# InternetButtonBuzzer.net
KiCad netlist of a schematic drawn in EAGLE
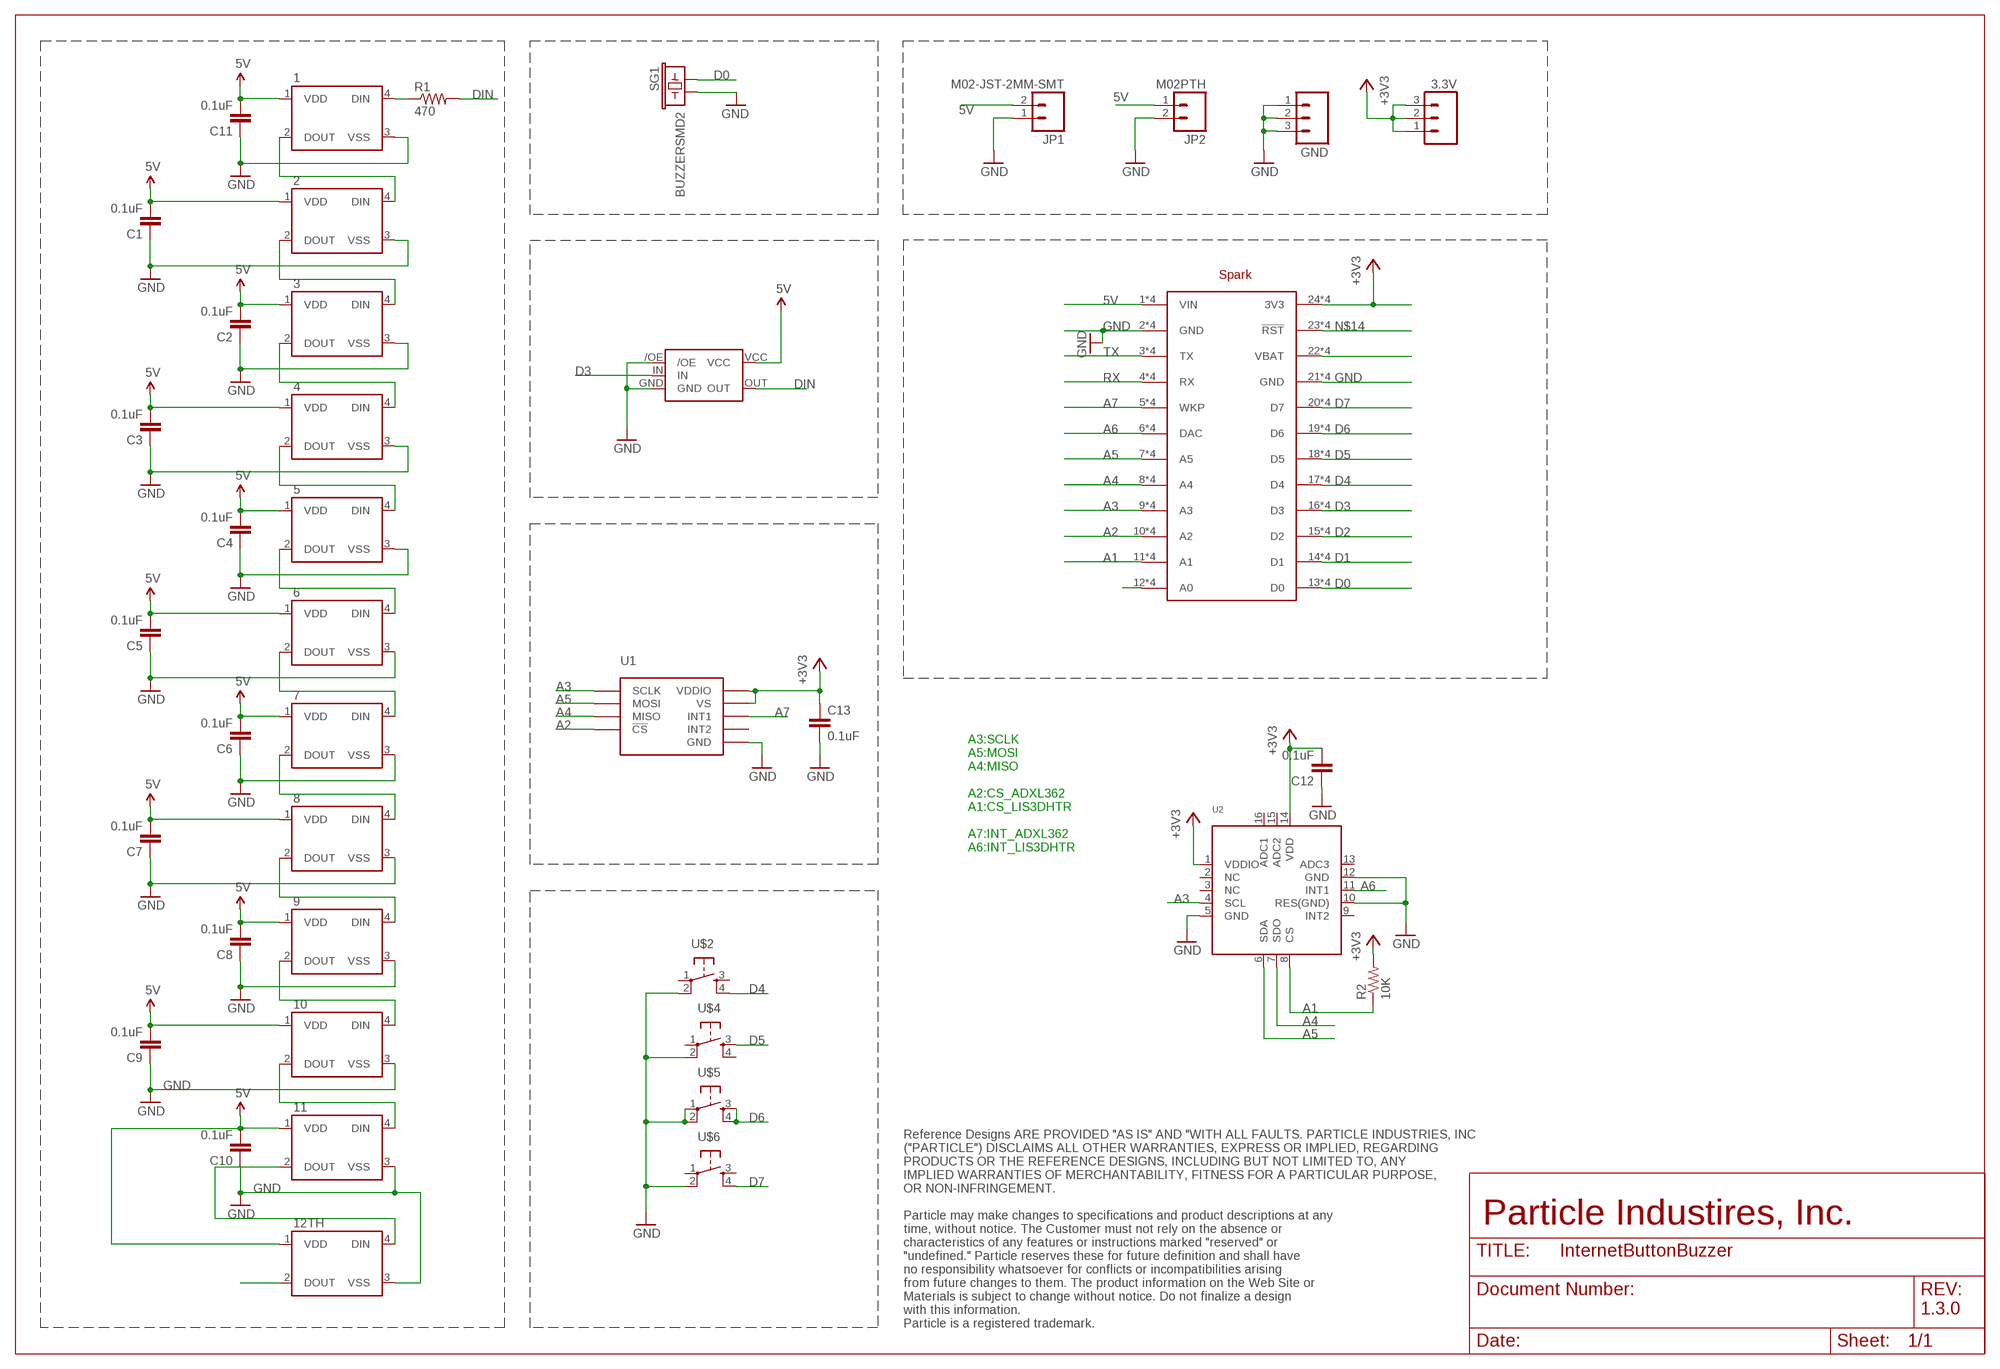
[diagram p0: schematic, sheet 1]

(export (version "E")
  (design (tool "Eeschema 10.0.6"))
  (components
    (comp (ref "1")
      (value "WS2812B")
      (footprint "eagle-import:WS2812B")
      (libsource (lib "eagle-import") (part "SparkFun-LED_WS2812B"))
    )
    (comp (ref "2")
      (value "WS2812B")
      (footprint "eagle-import:WS2812B")
      (libsource (lib "eagle-import") (part "SparkFun-LED_WS2812B"))
    )
    (comp (ref "3")
      (value "WS2812B")
      (footprint "eagle-import:WS2812B")
      (libsource (lib "eagle-import") (part "SparkFun-LED_WS2812B"))
    )
    (comp (ref "3.3V")
      (value "M03LOCK_NO_SILK")
      (footprint "eagle-import:1X03_LOCK_NO_SILK")
      (libsource (lib "eagle-import") (part "M03LOCK_NO_SILK"))
    )
    (comp (ref "4")
      (value "WS2812B")
      (footprint "eagle-import:WS2812B")
      (libsource (lib "eagle-import") (part "SparkFun-LED_WS2812B"))
    )
    (comp (ref "5")
      (value "WS2812B")
      (footprint "eagle-import:WS2812B")
      (libsource (lib "eagle-import") (part "SparkFun-LED_WS2812B"))
    )
    (comp (ref "6")
      (value "WS2812B")
      (footprint "eagle-import:WS2812B")
      (libsource (lib "eagle-import") (part "SparkFun-LED_WS2812B"))
    )
    (comp (ref "7")
      (value "WS2812B")
      (footprint "eagle-import:WS2812B")
      (libsource (lib "eagle-import") (part "SparkFun-LED_WS2812B"))
    )
    (comp (ref "8")
      (value "WS2812B")
      (footprint "eagle-import:WS2812B")
      (libsource (lib "eagle-import") (part "SparkFun-LED_WS2812B"))
    )
    (comp (ref "9")
      (value "WS2812B")
      (footprint "eagle-import:WS2812B")
      (libsource (lib "eagle-import") (part "SparkFun-LED_WS2812B"))
    )
    (comp (ref "10")
      (value "WS2812B")
      (footprint "eagle-import:WS2812B")
      (libsource (lib "eagle-import") (part "SparkFun-LED_WS2812B"))
    )
    (comp (ref "11")
      (value "WS2812B")
      (footprint "eagle-import:WS2812B")
      (libsource (lib "eagle-import") (part "SparkFun-LED_WS2812B"))
    )
    (comp (ref "12TH")
      (value "WS2812B")
      (footprint "eagle-import:NOCREAM_WS2812B")
      (libsource (lib "eagle-import") (part "WS2812B"))
    )
    (comp (ref "C1")
      (value "0.1uF")
      (footprint "eagle-import:0603-CAP")
      (libsource (lib "eagle-import") (part "15PF-50V-5%(0603)"))
    )
    (comp (ref "C2")
      (value "0.1uF")
      (footprint "eagle-import:0603-CAP")
      (libsource (lib "eagle-import") (part "15PF-50V-5%(0603)"))
    )
    (comp (ref "C3")
      (value "0.1uF")
      (footprint "eagle-import:0603-CAP")
      (libsource (lib "eagle-import") (part "15PF-50V-5%(0603)"))
    )
    (comp (ref "C4")
      (value "0.1uF")
      (footprint "eagle-import:0603-CAP")
      (libsource (lib "eagle-import") (part "15PF-50V-5%(0603)"))
    )
    (comp (ref "C5")
      (value "0.1uF")
      (footprint "eagle-import:0603-CAP")
      (libsource (lib "eagle-import") (part "15PF-50V-5%(0603)"))
    )
    (comp (ref "C6")
      (value "0.1uF")
      (footprint "eagle-import:0603-CAP")
      (libsource (lib "eagle-import") (part "15PF-50V-5%(0603)"))
    )
    (comp (ref "C7")
      (value "0.1uF")
      (footprint "eagle-import:0603-CAP")
      (libsource (lib "eagle-import") (part "15PF-50V-5%(0603)"))
    )
    (comp (ref "C8")
      (value "0.1uF")
      (footprint "eagle-import:0603-CAP")
      (libsource (lib "eagle-import") (part "15PF-50V-5%(0603)"))
    )
    (comp (ref "C9")
      (value "0.1uF")
      (footprint "eagle-import:0603-CAP")
      (libsource (lib "eagle-import") (part "15PF-50V-5%(0603)"))
    )
    (comp (ref "C10")
      (value "0.1uF")
      (footprint "eagle-import:0603-CAP")
      (libsource (lib "eagle-import") (part "15PF-50V-5%(0603)"))
    )
    (comp (ref "C11")
      (value "0.1uF")
      (footprint "eagle-import:0603-CAP")
      (libsource (lib "eagle-import") (part "15PF-50V-5%(0603)"))
    )
    (comp (ref "C12")
      (value "0.1uF")
      (footprint "eagle-import:0603-CAP")
      (libsource (lib "eagle-import") (part "CAP0603-CAP"))
    )
    (comp (ref "C13")
      (value "0.1uF")
      (footprint "eagle-import:0603-CAP")
      (libsource (lib "eagle-import") (part "CAP0603-CAP"))
    )
    (comp (ref "GND")
      (value "M03LOCK_NO_SILK")
      (footprint "eagle-import:1X03_LOCK_NO_SILK")
      (libsource (lib "eagle-import") (part "M03LOCK_NO_SILK"))
    )
    (comp (ref "JP1")
      (value "M02-JST-2MM-SMT")
      (footprint "eagle-import:JST-2-SMD")
      (libsource (lib "eagle-import") (part "M02-JST-2MM-SMT"))
    )
    (comp (ref "JP2")
      (value "M02PTH")
      (footprint "eagle-import:1X02")
      (libsource (lib "eagle-import") (part "M02PTH"))
    )
    (comp (ref "R1")
      (value "470")
      (footprint "eagle-import:0603-RES")
      (libsource (lib "eagle-import") (part "470OHM1/10W1%(0603)"))
    )
    (comp (ref "R2")
      (value "10K")
      (footprint "eagle-import:0603-RES")
      (libsource (lib "eagle-import") (part "470OHM1/10W1%(0603)"))
    )
    (comp (ref "SG1")
      (value "BUZZERSMD2")
      (footprint "eagle-import:BUZZER-CCV")
      (libsource (lib "eagle-import") (part "BUZZERSMD2"))
    )
    (comp (ref "U$2")
      (value "12MM_TACTILE_SWITCH")
      (footprint "eagle-import:12MM_TACTILE_SWITCH")
      (libsource (lib "eagle-import") (part "12MM_TACTILE_SWITCH"))
    )
    (comp (ref "U$3")
      (value "SPARK_LOGO_WITH_PLANE")
      (footprint "eagle-import:SPARK_LOGO_PLUS_PLANE")
      (libsource (lib "eagle-import") (part "SPARK_LOGO_WITH_PLANE"))
    )
    (comp (ref "U$4")
      (value "12MM_TACTILE_SWITCH")
      (footprint "eagle-import:12MM_TACTILE_SWITCH")
      (libsource (lib "eagle-import") (part "12MM_TACTILE_SWITCH"))
    )
    (comp (ref "U$5")
      (value "12MM_TACTILE_SWITCH")
      (footprint "eagle-import:12MM_TACTILE_SWITCH")
      (libsource (lib "eagle-import") (part "12MM_TACTILE_SWITCH"))
    )
    (comp (ref "U$6")
      (value "12MM_TACTILE_SWITCH")
      (footprint "eagle-import:12MM_TACTILE_SWITCH")
      (libsource (lib "eagle-import") (part "12MM_TACTILE_SWITCH"))
    )
    (comp (ref "U$7")
      (value "SPARK_COREDUAL_HEADER")
      (footprint "eagle-import:SPARK_CORE_DUAL_HEADER")
      (libsource (lib "eagle-import") (part "SPARK_COREDUAL_HEADER"))
    )
    (comp (ref "U$8")
      (value "NL17SZ125SOT553")
      (footprint "eagle-import:SOT-553")
      (libsource (lib "eagle-import") (part "NL17SZ125SOT553"))
    )
    (comp (ref "U1")
      (value "ADXL362ADXL362-1:1")
      (footprint "eagle-import:ADXL362-1_1")
      (libsource (lib "eagle-import") (part "ADXL362ADXL362-1{colon}1"))
    )
    (comp (ref "U2")
      (value "ACCEL_LIS3DHTR")
      (footprint "eagle-import:LGA16_3X3MM")
      (libsource (lib "eagle-import") (part "ACCEL_LIS3DHTR"))
    )
  )
  (nets
    (net (code "1") (name "+3V3") (class "Default")
      (node (ref "3.3V") (pin "1") (pinfunction "1_1") (pintype "passive"))
      (node (ref "3.3V") (pin "2") (pinfunction "2_2") (pintype "passive"))
      (node (ref "3.3V") (pin "3") (pinfunction "3_3") (pintype "passive"))
      (node (ref "C12") (pin "2") (pinfunction "2_2") (pintype "passive"))
      (node (ref "C13") (pin "1") (pinfunction "1_1") (pintype "passive"))
      (node (ref "R2") (pin "2") (pinfunction "2_2") (pintype "passive"))
      (node (ref "U$7") (pin "24") (pinfunction "3V3_24") (pintype "power_in"))
      (node (ref "U$7") (pin "24B") (pinfunction "3V3_24B") (pintype "power_in"))
      (node (ref "U$7") (pin "@24") (pinfunction "3V3_@24") (pintype "power_in"))
      (node (ref "U$7") (pin "@24B") (pinfunction "3V3_@24B") (pintype "power_in"))
      (node (ref "U1") (pin "P$1") (pinfunction "VDDIO_P$1") (pintype "bidirectional"))
      (node (ref "U1") (pin "P$14") (pinfunction "VS_P$14") (pintype "bidirectional"))
      (node (ref "U2") (pin "1") (pinfunction "VDDIO_1") (pintype "power_in"))
      (node (ref "U2") (pin "14") (pinfunction "VDD_14") (pintype "power_in"))
    )
    (net (code "2") (name "/A1") (class "Default")
      (node (ref "R2") (pin "1") (pinfunction "1_1") (pintype "passive"))
      (node (ref "U$7") (pin "11") (pinfunction "A1_11") (pintype "bidirectional"))
      (node (ref "U$7") (pin "11B") (pinfunction "A1_11B") (pintype "bidirectional"))
      (node (ref "U$7") (pin "@11") (pinfunction "A1_@11") (pintype "bidirectional"))
      (node (ref "U$7") (pin "@11B") (pinfunction "A1_@11B") (pintype "bidirectional"))
      (node (ref "U2") (pin "8") (pinfunction "CS_8") (pintype "input"))
    )
    (net (code "3") (name "/A2") (class "Default")
      (node (ref "U$7") (pin "10") (pinfunction "A2_10") (pintype "bidirectional"))
      (node (ref "U$7") (pin "10B") (pinfunction "A2_10B") (pintype "bidirectional"))
      (node (ref "U$7") (pin "@10") (pinfunction "A2_@10") (pintype "bidirectional"))
      (node (ref "U$7") (pin "@10B") (pinfunction "A2_@10B") (pintype "bidirectional"))
      (node (ref "U1") (pin "P$8") (pinfunction "~{CS}_P$8") (pintype "bidirectional"))
    )
    (net (code "4") (name "/A3") (class "Default")
      (node (ref "U$7") (pin "9") (pinfunction "A3_9") (pintype "bidirectional"))
      (node (ref "U$7") (pin "9B") (pinfunction "A3_9B") (pintype "bidirectional"))
      (node (ref "U$7") (pin "@9") (pinfunction "A3_@9") (pintype "bidirectional"))
      (node (ref "U$7") (pin "@9B") (pinfunction "A3_@9B") (pintype "bidirectional"))
      (node (ref "U1") (pin "P$4") (pinfunction "SCLK_P$4") (pintype "bidirectional"))
      (node (ref "U2") (pin "4") (pinfunction "SCL_4") (pintype "bidirectional"))
    )
    (net (code "5") (name "/A4") (class "Default")
      (node (ref "U$7") (pin "8") (pinfunction "A4_8") (pintype "bidirectional"))
      (node (ref "U$7") (pin "8B") (pinfunction "A4_8B") (pintype "bidirectional"))
      (node (ref "U$7") (pin "@8") (pinfunction "A4_@8") (pintype "bidirectional"))
      (node (ref "U$7") (pin "@8B") (pinfunction "A4_@8B") (pintype "bidirectional"))
      (node (ref "U1") (pin "P$7") (pinfunction "MISO_P$7") (pintype "bidirectional"))
      (node (ref "U2") (pin "7") (pinfunction "SDO_7") (pintype "bidirectional"))
    )
    (net (code "6") (name "/A5") (class "Default")
      (node (ref "U$7") (pin "7") (pinfunction "A5_7") (pintype "bidirectional"))
      (node (ref "U$7") (pin "7B") (pinfunction "A5_7B") (pintype "bidirectional"))
      (node (ref "U$7") (pin "@7") (pinfunction "A5_@7") (pintype "bidirectional"))
      (node (ref "U$7") (pin "@7B") (pinfunction "A5_@7B") (pintype "bidirectional"))
      (node (ref "U1") (pin "P$6") (pinfunction "MOSI_P$6") (pintype "bidirectional"))
      (node (ref "U2") (pin "6") (pinfunction "SDA_6") (pintype "bidirectional"))
    )
    (net (code "7") (name "/A6") (class "Default")
      (node (ref "U$7") (pin "6") (pinfunction "DAC_6") (pintype "bidirectional"))
      (node (ref "U$7") (pin "6B") (pinfunction "DAC_6B") (pintype "bidirectional"))
      (node (ref "U$7") (pin "@6") (pinfunction "DAC_@6") (pintype "bidirectional"))
      (node (ref "U$7") (pin "@6B") (pinfunction "DAC_@6B") (pintype "bidirectional"))
      (node (ref "U2") (pin "11") (pinfunction "INT1_11") (pintype "output"))
    )
    (net (code "8") (name "/A7") (class "Default")
      (node (ref "U$7") (pin "5") (pinfunction "WKP_5") (pintype "bidirectional"))
      (node (ref "U$7") (pin "5B") (pinfunction "WKP_5B") (pintype "bidirectional"))
      (node (ref "U$7") (pin "@5") (pinfunction "WKP_@5") (pintype "bidirectional"))
      (node (ref "U$7") (pin "@5B") (pinfunction "WKP_@5B") (pintype "bidirectional"))
      (node (ref "U1") (pin "P$11") (pinfunction "INT1_P$11") (pintype "bidirectional"))
    )
    (net (code "9") (name "/D0") (class "Default")
      (node (ref "SG1") (pin "+") (pinfunction "1_+") (pintype "passive"))
      (node (ref "U$7") (pin "13") (pinfunction "D0_13") (pintype "bidirectional"))
      (node (ref "U$7") (pin "13B") (pinfunction "D0_13B") (pintype "bidirectional"))
      (node (ref "U$7") (pin "@13") (pinfunction "D0_@13") (pintype "bidirectional"))
      (node (ref "U$7") (pin "@13B") (pinfunction "D0_@13B") (pintype "bidirectional"))
    )
    (net (code "10") (name "/D1") (class "Default")
      (node (ref "U$7") (pin "14") (pinfunction "D1_14") (pintype "bidirectional"))
      (node (ref "U$7") (pin "14B") (pinfunction "D1_14B") (pintype "bidirectional"))
      (node (ref "U$7") (pin "@14") (pinfunction "D1_@14") (pintype "bidirectional"))
      (node (ref "U$7") (pin "@14B") (pinfunction "D1_@14B") (pintype "bidirectional"))
    )
    (net (code "11") (name "/D2") (class "Default")
      (node (ref "U$7") (pin "15") (pinfunction "D2_15") (pintype "bidirectional"))
      (node (ref "U$7") (pin "15B") (pinfunction "D2_15B") (pintype "bidirectional"))
      (node (ref "U$7") (pin "@15") (pinfunction "D2_@15") (pintype "bidirectional"))
      (node (ref "U$7") (pin "@15B") (pinfunction "D2_@15B") (pintype "bidirectional"))
    )
    (net (code "12") (name "/D3") (class "Default")
      (node (ref "U$7") (pin "16") (pinfunction "D3_16") (pintype "bidirectional"))
      (node (ref "U$7") (pin "16B") (pinfunction "D3_16B") (pintype "bidirectional"))
      (node (ref "U$7") (pin "@16") (pinfunction "D3_@16") (pintype "bidirectional"))
      (node (ref "U$7") (pin "@16B") (pinfunction "D3_@16B") (pintype "bidirectional"))
      (node (ref "U$8") (pin "IN") (pinfunction "IN_IN") (pintype "bidirectional"))
    )
    (net (code "13") (name "/D4") (class "Default")
      (node (ref "U$2") (pin "4") (pinfunction "4_4") (pintype "passive"))
      (node (ref "U$7") (pin "17") (pinfunction "D4_17") (pintype "bidirectional"))
      (node (ref "U$7") (pin "17B") (pinfunction "D4_17B") (pintype "bidirectional"))
      (node (ref "U$7") (pin "@17") (pinfunction "D4_@17") (pintype "bidirectional"))
      (node (ref "U$7") (pin "@17B") (pinfunction "D4_@17B") (pintype "bidirectional"))
    )
    (net (code "14") (name "/D5") (class "Default")
      (node (ref "U$4") (pin "3") (pinfunction "3_3") (pintype "passive"))
      (node (ref "U$7") (pin "18") (pinfunction "D5_18") (pintype "bidirectional"))
      (node (ref "U$7") (pin "18B") (pinfunction "D5_18B") (pintype "bidirectional"))
      (node (ref "U$7") (pin "@18") (pinfunction "D5_@18") (pintype "bidirectional"))
      (node (ref "U$7") (pin "@18B") (pinfunction "D5_@18B") (pintype "bidirectional"))
    )
    (net (code "15") (name "/D6") (class "Default")
      (node (ref "U$5") (pin "3") (pinfunction "3_3") (pintype "passive"))
      (node (ref "U$5") (pin "4") (pinfunction "4_4") (pintype "passive"))
      (node (ref "U$7") (pin "19") (pinfunction "D6_19") (pintype "bidirectional"))
      (node (ref "U$7") (pin "19B") (pinfunction "D6_19B") (pintype "bidirectional"))
      (node (ref "U$7") (pin "@19") (pinfunction "D6_@19") (pintype "bidirectional"))
      (node (ref "U$7") (pin "@19B") (pinfunction "D6_@19B") (pintype "bidirectional"))
    )
    (net (code "16") (name "/D7") (class "Default")
      (node (ref "U$6") (pin "4") (pinfunction "4_4") (pintype "passive"))
      (node (ref "U$7") (pin "20") (pinfunction "D7_20") (pintype "bidirectional"))
      (node (ref "U$7") (pin "20B") (pinfunction "D7_20B") (pintype "bidirectional"))
      (node (ref "U$7") (pin "@20") (pinfunction "D7_@20") (pintype "bidirectional"))
      (node (ref "U$7") (pin "@20B") (pinfunction "D7_@20B") (pintype "bidirectional"))
    )
    (net (code "17") (name "/DIN") (class "Default")
      (node (ref "R1") (pin "2") (pinfunction "2_2") (pintype "passive"))
      (node (ref "U$8") (pin "OUT") (pinfunction "OUT_OUT") (pintype "bidirectional"))
    )
    (net (code "18") (name "/N$14") (class "Default")
      (node (ref "U$7") (pin "23") (pinfunction "~{RST}_23") (pintype "bidirectional"))
      (node (ref "U$7") (pin "23B") (pinfunction "~{RST}_23B") (pintype "bidirectional"))
      (node (ref "U$7") (pin "@23") (pinfunction "~{RST}_@23") (pintype "bidirectional"))
      (node (ref "U$7") (pin "@23B") (pinfunction "~{RST}_@23B") (pintype "bidirectional"))
    )
    (net (code "19") (name "/RX") (class "Default")
      (node (ref "U$7") (pin "4") (pinfunction "RX_4") (pintype "bidirectional"))
      (node (ref "U$7") (pin "4B") (pinfunction "RX_4B") (pintype "bidirectional"))
      (node (ref "U$7") (pin "@4") (pinfunction "RX_@4") (pintype "bidirectional"))
      (node (ref "U$7") (pin "@4B") (pinfunction "RX_@4B") (pintype "bidirectional"))
    )
    (net (code "20") (name "/TX") (class "Default")
      (node (ref "U$7") (pin "3") (pinfunction "TX_3") (pintype "bidirectional"))
      (node (ref "U$7") (pin "3B") (pinfunction "TX_3B") (pintype "bidirectional"))
      (node (ref "U$7") (pin "@3") (pinfunction "TX_@3") (pintype "bidirectional"))
      (node (ref "U$7") (pin "@3B") (pinfunction "TX_@3B") (pintype "bidirectional"))
    )
    (net (code "21") (name "5V") (class "Default")
      (node (ref "1") (pin "1") (pinfunction "VDD_1") (pintype "power_in"))
      (node (ref "10") (pin "1") (pinfunction "VDD_1") (pintype "power_in"))
      (node (ref "11") (pin "1") (pinfunction "VDD_1") (pintype "power_in"))
      (node (ref "12TH") (pin "1") (pinfunction "VDD_1") (pintype "power_in"))
      (node (ref "2") (pin "1") (pinfunction "VDD_1") (pintype "power_in"))
      (node (ref "3") (pin "1") (pinfunction "VDD_1") (pintype "power_in"))
      (node (ref "4") (pin "1") (pinfunction "VDD_1") (pintype "power_in"))
      (node (ref "5") (pin "1") (pinfunction "VDD_1") (pintype "power_in"))
      (node (ref "6") (pin "1") (pinfunction "VDD_1") (pintype "power_in"))
      (node (ref "7") (pin "1") (pinfunction "VDD_1") (pintype "power_in"))
      (node (ref "8") (pin "1") (pinfunction "VDD_1") (pintype "power_in"))
      (node (ref "9") (pin "1") (pinfunction "VDD_1") (pintype "power_in"))
      (node (ref "C1") (pin "2") (pinfunction "2_2") (pintype "passive"))
      (node (ref "C10") (pin "2") (pinfunction "2_2") (pintype "passive"))
      (node (ref "C11") (pin "2") (pinfunction "2_2") (pintype "passive"))
      (node (ref "C2") (pin "2") (pinfunction "2_2") (pintype "passive"))
      (node (ref "C3") (pin "2") (pinfunction "2_2") (pintype "passive"))
      (node (ref "C4") (pin "2") (pinfunction "2_2") (pintype "passive"))
      (node (ref "C5") (pin "2") (pinfunction "2_2") (pintype "passive"))
      (node (ref "C6") (pin "2") (pinfunction "2_2") (pintype "passive"))
      (node (ref "C7") (pin "2") (pinfunction "2_2") (pintype "passive"))
      (node (ref "C8") (pin "2") (pinfunction "2_2") (pintype "passive"))
      (node (ref "C9") (pin "2") (pinfunction "2_2") (pintype "passive"))
      (node (ref "JP1") (pin "2") (pinfunction "1_2") (pintype "passive"))
      (node (ref "JP2") (pin "1") (pinfunction "1_1") (pintype "passive"))
      (node (ref "U$7") (pin "1") (pinfunction "VIN_1") (pintype "power_in"))
      (node (ref "U$7") (pin "1B") (pinfunction "VIN_1B") (pintype "power_in"))
      (node (ref "U$7") (pin "@1") (pinfunction "VIN_@1") (pintype "power_in"))
      (node (ref "U$7") (pin "@1B") (pinfunction "VIN_@1B") (pintype "power_in"))
      (node (ref "U$8") (pin "VCC") (pinfunction "VCC_VCC") (pintype "bidirectional"))
    )
    (net (code "22") (name "GND") (class "Default")
      (node (ref "1") (pin "3") (pinfunction "VSS_3") (pintype "power_in"))
      (node (ref "10") (pin "3") (pinfunction "VSS_3") (pintype "power_in"))
      (node (ref "11") (pin "3") (pinfunction "VSS_3") (pintype "power_in"))
      (node (ref "12TH") (pin "3") (pinfunction "VSS_3") (pintype "power_in"))
      (node (ref "2") (pin "3") (pinfunction "VSS_3") (pintype "power_in"))
      (node (ref "3") (pin "3") (pinfunction "VSS_3") (pintype "power_in"))
      (node (ref "4") (pin "3") (pinfunction "VSS_3") (pintype "power_in"))
      (node (ref "5") (pin "3") (pinfunction "VSS_3") (pintype "power_in"))
      (node (ref "6") (pin "3") (pinfunction "VSS_3") (pintype "power_in"))
      (node (ref "7") (pin "3") (pinfunction "VSS_3") (pintype "power_in"))
      (node (ref "8") (pin "3") (pinfunction "VSS_3") (pintype "power_in"))
      (node (ref "9") (pin "3") (pinfunction "VSS_3") (pintype "power_in"))
      (node (ref "C1") (pin "1") (pinfunction "1_1") (pintype "passive"))
      (node (ref "C10") (pin "1") (pinfunction "1_1") (pintype "passive"))
      (node (ref "C11") (pin "1") (pinfunction "1_1") (pintype "passive"))
      (node (ref "C12") (pin "1") (pinfunction "1_1") (pintype "passive"))
      (node (ref "C13") (pin "2") (pinfunction "2_2") (pintype "passive"))
      (node (ref "C2") (pin "1") (pinfunction "1_1") (pintype "passive"))
      (node (ref "C3") (pin "1") (pinfunction "1_1") (pintype "passive"))
      (node (ref "C4") (pin "1") (pinfunction "1_1") (pintype "passive"))
      (node (ref "C5") (pin "1") (pinfunction "1_1") (pintype "passive"))
      (node (ref "C6") (pin "1") (pinfunction "1_1") (pintype "passive"))
      (node (ref "C7") (pin "1") (pinfunction "1_1") (pintype "passive"))
      (node (ref "C8") (pin "1") (pinfunction "1_1") (pintype "passive"))
      (node (ref "C9") (pin "1") (pinfunction "1_1") (pintype "passive"))
      (node (ref "GND") (pin "1") (pinfunction "1_1") (pintype "passive"))
      (node (ref "GND") (pin "2") (pinfunction "2_2") (pintype "passive"))
      (node (ref "GND") (pin "3") (pinfunction "3_3") (pintype "passive"))
      (node (ref "JP1") (pin "1") (pinfunction "2_1") (pintype "passive"))
      (node (ref "JP2") (pin "2") (pinfunction "2_2") (pintype "passive"))
      (node (ref "SG1") (pin "-") (pinfunction "2_-") (pintype "passive"))
      (node (ref "U$2") (pin "2") (pinfunction "2_2") (pintype "passive"))
      (node (ref "U$4") (pin "2") (pinfunction "2_2") (pintype "passive"))
      (node (ref "U$5") (pin "1") (pinfunction "1_1") (pintype "passive"))
      (node (ref "U$5") (pin "2") (pinfunction "2_2") (pintype "passive"))
      (node (ref "U$6") (pin "2") (pinfunction "2_2") (pintype "passive"))
      (node (ref "U$7") (pin "2") (pinfunction "GND_2") (pintype "power_in"))
      (node (ref "U$7") (pin "21") (pinfunction "GND_21") (pintype "power_in"))
      (node (ref "U$7") (pin "21B") (pinfunction "GND_21B") (pintype "power_in"))
      (node (ref "U$7") (pin "2B") (pinfunction "GND_2B") (pintype "power_in"))
      (node (ref "U$7") (pin "@2") (pinfunction "GND_@2") (pintype "power_in"))
      (node (ref "U$7") (pin "@21") (pinfunction "GND_@21") (pintype "power_in"))
      (node (ref "U$7") (pin "@21B") (pinfunction "GND_@21B") (pintype "power_in"))
      (node (ref "U$7") (pin "@2B") (pinfunction "GND_@2B") (pintype "power_in"))
      (node (ref "U$8") (pin "/OE") (pinfunction "/OE_/OE") (pintype "bidirectional"))
      (node (ref "U$8") (pin "GND") (pinfunction "GND_GND") (pintype "bidirectional"))
      (node (ref "U1") (pin "P$12") (pinfunction "GND_P$12") (pintype "bidirectional"))
      (node (ref "U1") (pin "P$13") (pinfunction "GND_P$13") (pintype "bidirectional"))
      (node (ref "U1") (pin "P$16") (pinfunction "GND_P$16") (pintype "bidirectional"))
      (node (ref "U2") (pin "10") (pinfunction "RES(GND)_10") (pintype "bidirectional"))
      (node (ref "U2") (pin "12") (pinfunction "GND_12") (pintype "power_in"))
      (node (ref "U2") (pin "5") (pinfunction "GND_5") (pintype "power_in"))
    )
    (net (code "23") (name "Net-(1-DIN)") (class "Default")
      (node (ref "1") (pin "4") (pinfunction "DIN_4") (pintype "input"))
      (node (ref "R1") (pin "1") (pinfunction "1_1") (pintype "passive"))
    )
    (net (code "24") (name "Net-(1-DOUT)") (class "Default")
      (node (ref "1") (pin "2") (pinfunction "DOUT_2") (pintype "output"))
      (node (ref "2") (pin "4") (pinfunction "DIN_4") (pintype "input"))
    )
    (net (code "25") (name "Net-(2-DOUT)") (class "Default")
      (node (ref "2") (pin "2") (pinfunction "DOUT_2") (pintype "output"))
      (node (ref "3") (pin "4") (pinfunction "DIN_4") (pintype "input"))
    )
    (net (code "26") (name "Net-(3-DOUT)") (class "Default")
      (node (ref "3") (pin "2") (pinfunction "DOUT_2") (pintype "output"))
      (node (ref "4") (pin "4") (pinfunction "DIN_4") (pintype "input"))
    )
    (net (code "27") (name "Net-(4-DOUT)") (class "Default")
      (node (ref "4") (pin "2") (pinfunction "DOUT_2") (pintype "output"))
      (node (ref "5") (pin "4") (pinfunction "DIN_4") (pintype "input"))
    )
    (net (code "28") (name "Net-(5-DOUT)") (class "Default")
      (node (ref "5") (pin "2") (pinfunction "DOUT_2") (pintype "output"))
      (node (ref "6") (pin "4") (pinfunction "DIN_4") (pintype "input"))
    )
    (net (code "29") (name "Net-(6-DOUT)") (class "Default")
      (node (ref "6") (pin "2") (pinfunction "DOUT_2") (pintype "output"))
      (node (ref "7") (pin "4") (pinfunction "DIN_4") (pintype "input"))
    )
    (net (code "30") (name "Net-(7-DOUT)") (class "Default")
      (node (ref "7") (pin "2") (pinfunction "DOUT_2") (pintype "output"))
      (node (ref "8") (pin "4") (pinfunction "DIN_4") (pintype "input"))
    )
    (net (code "31") (name "Net-(8-DOUT)") (class "Default")
      (node (ref "8") (pin "2") (pinfunction "DOUT_2") (pintype "output"))
      (node (ref "9") (pin "4") (pinfunction "DIN_4") (pintype "input"))
    )
    (net (code "32") (name "Net-(10-DIN)") (class "Default")
      (node (ref "10") (pin "4") (pinfunction "DIN_4") (pintype "input"))
      (node (ref "9") (pin "2") (pinfunction "DOUT_2") (pintype "output"))
    )
    (net (code "33") (name "Net-(10-DOUT)") (class "Default")
      (node (ref "10") (pin "2") (pinfunction "DOUT_2") (pintype "output"))
      (node (ref "11") (pin "4") (pinfunction "DIN_4") (pintype "input"))
    )
    (net (code "34") (name "Net-(11-DOUT)") (class "Default")
      (node (ref "11") (pin "2") (pinfunction "DOUT_2") (pintype "output"))
      (node (ref "12TH") (pin "4") (pinfunction "DIN_4") (pintype "input"))
    )
    (net (code "35") (name "Net-(U$7-A0-Pad12)") (class "Default")
      (node (ref "U$7") (pin "12") (pinfunction "A0_12") (pintype "bidirectional"))
      (node (ref "U$7") (pin "12B") (pinfunction "A0_12B") (pintype "bidirectional"))
      (node (ref "U$7") (pin "@12") (pinfunction "A0_@12") (pintype "bidirectional"))
      (node (ref "U$7") (pin "@12B") (pinfunction "A0_@12B") (pintype "bidirectional"))
    )
    (net (code "36") (name "Net-(U$7-VBAT-Pad22)") (class "Default")
      (node (ref "U$7") (pin "22") (pinfunction "VBAT_22") (pintype "power_in"))
      (node (ref "U$7") (pin "22B") (pinfunction "VBAT_22B") (pintype "power_in"))
      (node (ref "U$7") (pin "@22") (pinfunction "VBAT_@22") (pintype "power_in"))
      (node (ref "U$7") (pin "@22B") (pinfunction "VBAT_@22B") (pintype "power_in"))
    )
    (net (code "37") (name "unconnected-(12TH-DOUT-Pad2)") (class "Default")
      (node (ref "12TH") (pin "2") (pinfunction "DOUT_2") (pintype "output"))
    )
    (net (code "38") (name "unconnected-(U$2-Pad1)") (class "Default")
      (node (ref "U$2") (pin "1") (pinfunction "1_1") (pintype "passive"))
    )
    (net (code "39") (name "unconnected-(U$2-Pad3)") (class "Default")
      (node (ref "U$2") (pin "3") (pinfunction "3_3") (pintype "passive"))
    )
    (net (code "40") (name "unconnected-(U$4-Pad1)") (class "Default")
      (node (ref "U$4") (pin "1") (pinfunction "1_1") (pintype "passive"))
    )
    (net (code "41") (name "unconnected-(U$4-Pad4)") (class "Default")
      (node (ref "U$4") (pin "4") (pinfunction "4_4") (pintype "passive"))
    )
    (net (code "42") (name "unconnected-(U$6-Pad1)") (class "Default")
      (node (ref "U$6") (pin "1") (pinfunction "1_1") (pintype "passive"))
    )
    (net (code "43") (name "unconnected-(U$6-Pad3)") (class "Default")
      (node (ref "U$6") (pin "3") (pinfunction "3_3") (pintype "passive"))
    )
    (net (code "44") (name "unconnected-(U1-INT2-PadP$9)") (class "Default")
      (node (ref "U1") (pin "P$9") (pinfunction "INT2_P$9") (pintype "bidirectional"))
    )
    (net (code "45") (name "unconnected-(U2-ADC1-Pad16)") (class "Default")
      (node (ref "U2") (pin "16") (pinfunction "ADC1_16") (pintype "input"))
    )
    (net (code "46") (name "unconnected-(U2-ADC2-Pad15)") (class "Default")
      (node (ref "U2") (pin "15") (pinfunction "ADC2_15") (pintype "input"))
    )
    (net (code "47") (name "unconnected-(U2-ADC3-Pad13)") (class "Default")
      (node (ref "U2") (pin "13") (pinfunction "ADC3_13") (pintype "input"))
    )
    (net (code "48") (name "unconnected-(U2-INT2-Pad9)") (class "Default")
      (node (ref "U2") (pin "9") (pinfunction "INT2_9") (pintype "output"))
    )
    (net (code "49") (name "unconnected-(U2-NC-Pad2)") (class "Default")
      (node (ref "U2") (pin "2") (pinfunction "NC_2") (pintype "no_connect"))
    )
    (net (code "50") (name "unconnected-(U2-NC-Pad3)") (class "Default")
      (node (ref "U2") (pin "3") (pinfunction "NC_3") (pintype "no_connect"))
    )
  )
)
